# BLDC-DRIVER.net
KiCad netlist of a schematic drawn in Altium Designer
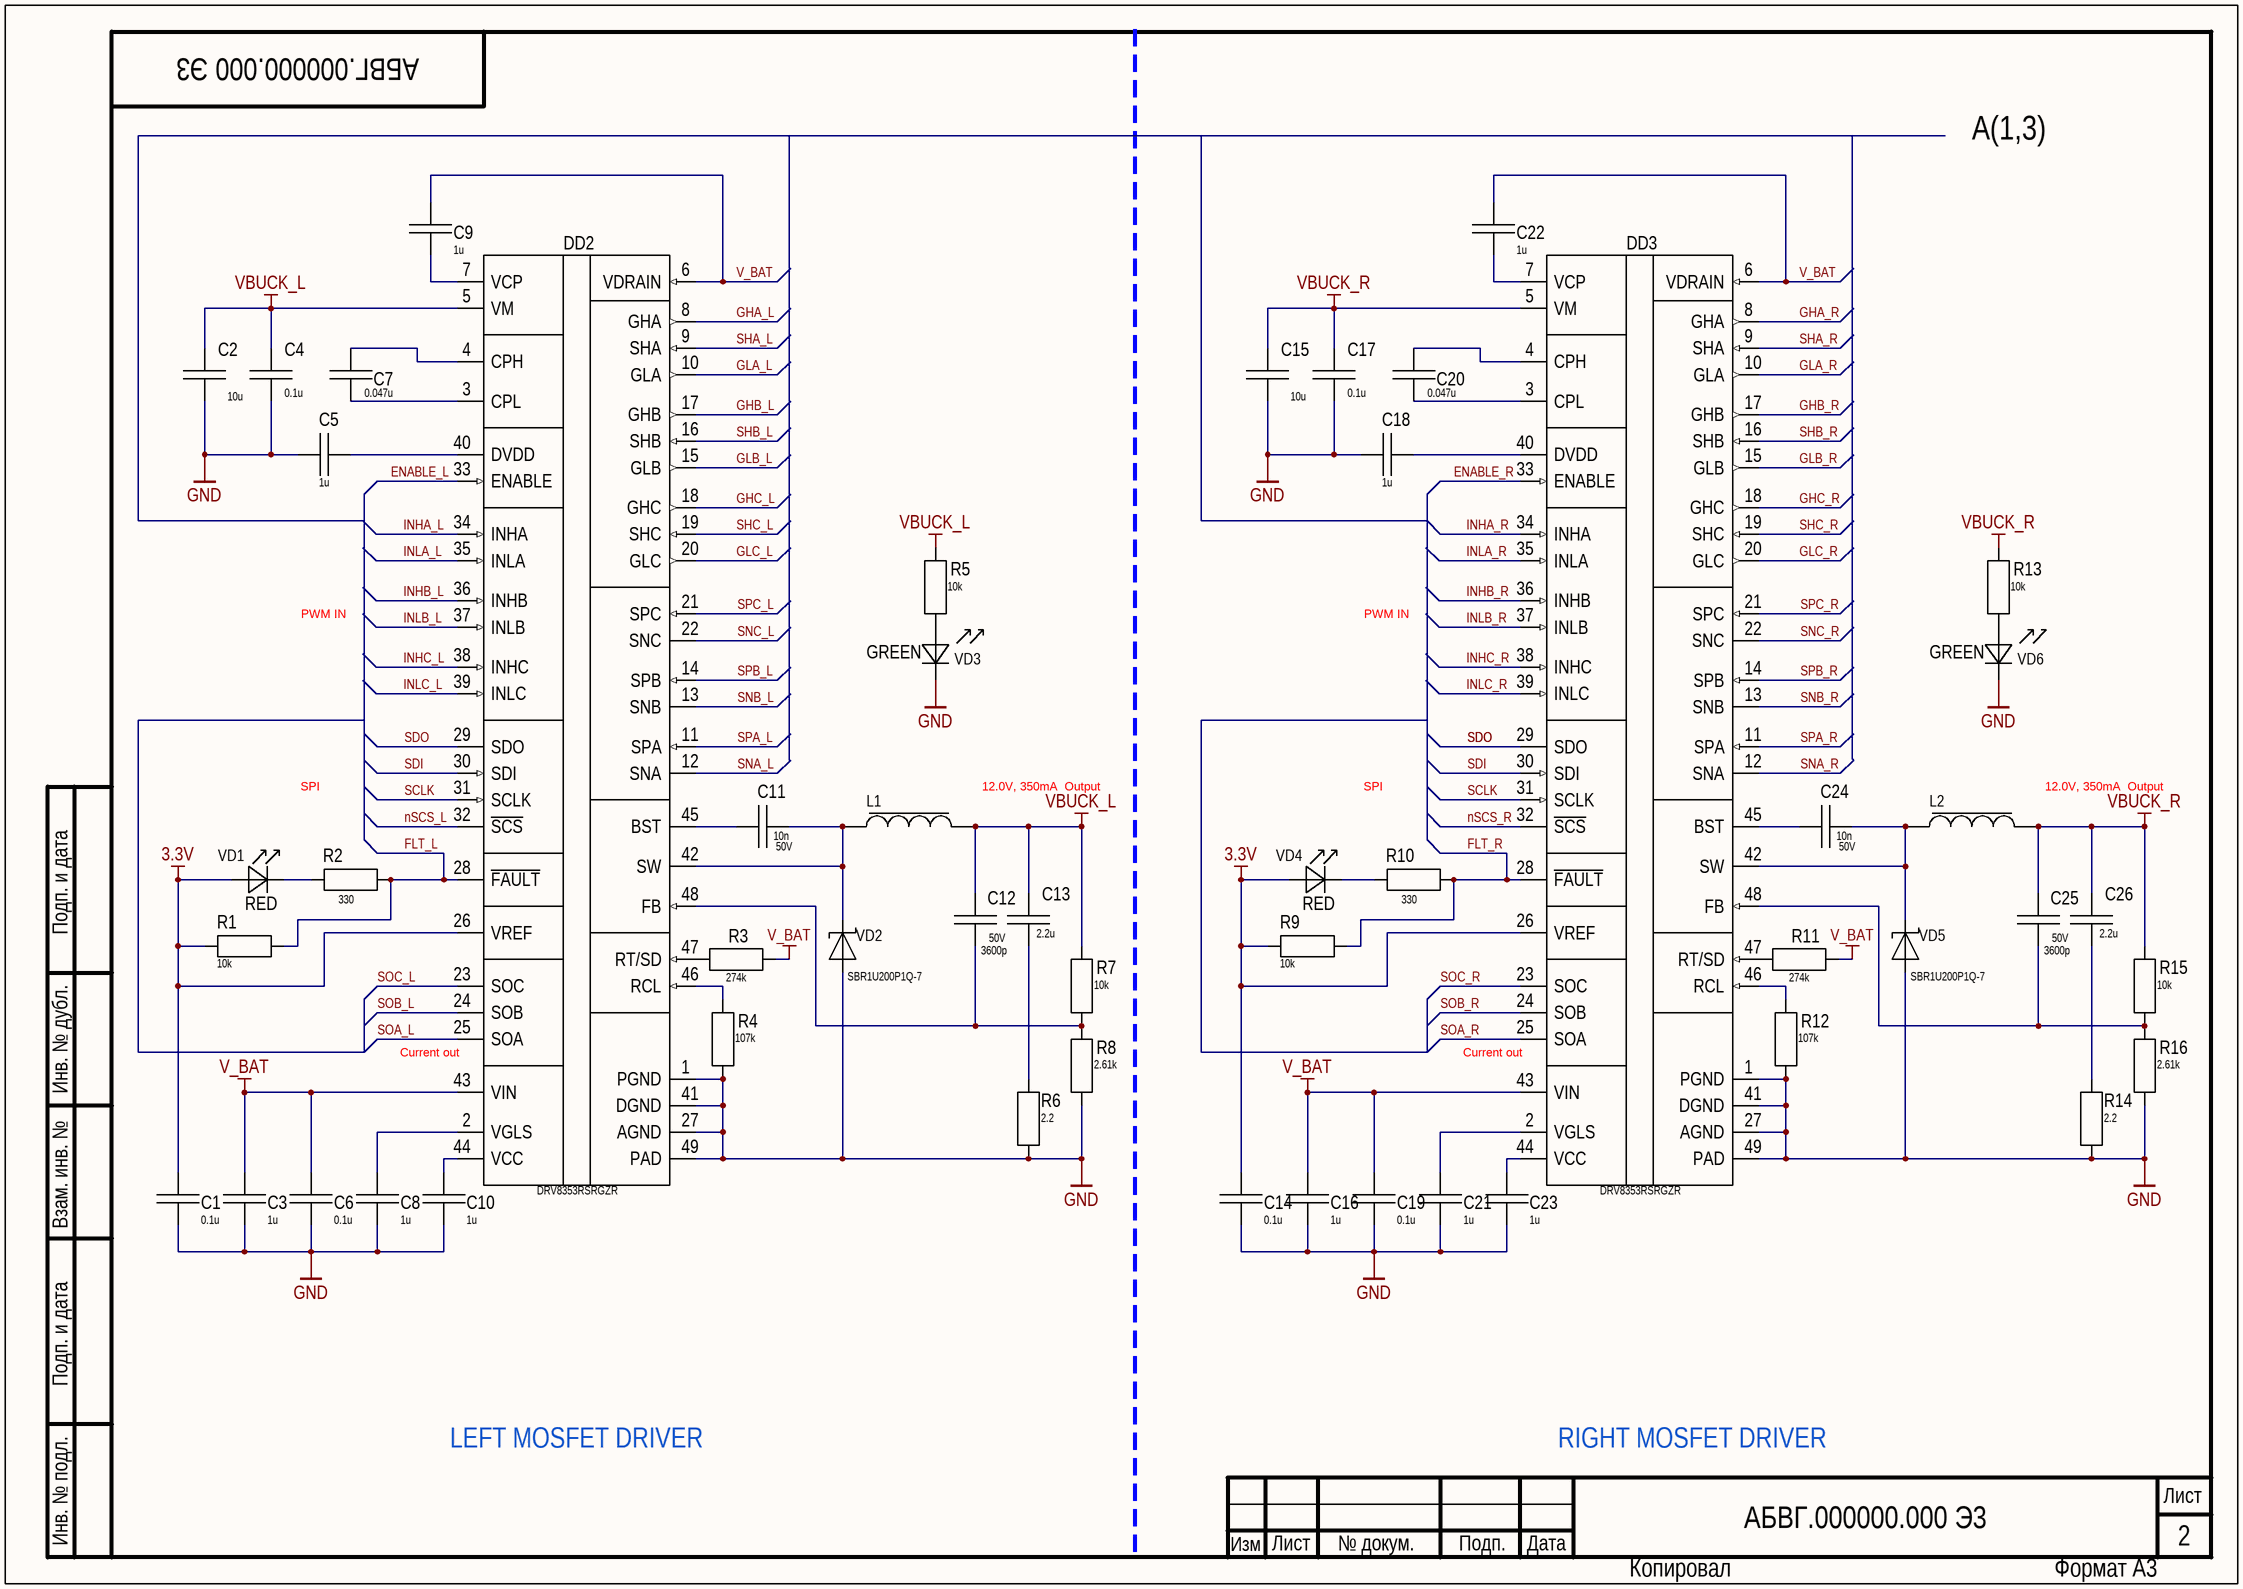
[diagram p0: BLDC-DRIVER.SchDoc]

(export (version "E")
  (design (tool "Eeschema 10.0.6"))
  (components
    (comp (ref "C1")
      (value "0.1u")
      (footprint "CAP: 0402")
      (fields
        (field (name "VOLTAGE") "10V")
        (field (name "PARTNUMBER") "C0402C104K8PAC")
        (field (name "MANUFACTURER") "Kemet")
      )
      (libsource (lib "Fider_Board_Lib") (part "CAP 0402"))
    )
    (comp (ref "C2")
      (value "10u")
      (footprint "CAP: 2220")
      (fields
        (field (name "VOLTAGE") "100V")
        (field (name "TOLERANCE") "10%")
        (field (name "PARTNUMBER") "CGA9N3X7S2A106K230KE")
      )
      (libsource (lib "BKM_SCH_Lib") (part "CAP 2220"))
    )
    (comp (ref "C3")
      (value "1u")
      (footprint "CAP: 1206")
      (fields (field (name "VOLTAGE") "100V") (field (name "TOLERANCE") "10%"))
      (libsource (lib "BKM_SCH_Lib") (part "CAP 1206"))
    )
    (comp (ref "C4")
      (value "0.1u")
      (footprint "CAP: 0805")
      (fields (field (name "VOLTAGE") "100V") (field (name "TOLERANCE") "10%"))
      (libsource (lib "BKM_SCH_Lib") (part "CAP 0805"))
    )
    (comp (ref "C5")
      (value "1u")
      (footprint "CAP: 0603")
      (fields (field (name "VOLTAGE") "16V") (field (name "TOLERANCE") "10%"))
      (libsource (lib "BKM_SCH_Lib") (part "CAP 0603"))
    )
    (comp (ref "C6")
      (value "0.1u")
      (footprint "CAP: 0805")
      (fields (field (name "VOLTAGE") "100V") (field (name "TOLERANCE") "10%"))
      (libsource (lib "BKM_SCH_Lib") (part "CAP 0805"))
    )
    (comp (ref "C7")
      (value "0.047u")
      (footprint "CAP: 0805")
      (fields (field (name "VOLTAGE") "100V") (field (name "TOLERANCE") "10%"))
      (libsource (lib "BKM_SCH_Lib") (part "CAP 0805"))
    )
    (comp (ref "C8")
      (value "1u")
      (footprint "CAP: 0603")
      (fields (field (name "VOLTAGE") "16V") (field (name "TOLERANCE") "10%"))
      (libsource (lib "BKM_SCH_Lib") (part "CAP 0603"))
    )
    (comp (ref "C9")
      (value "1u")
      (footprint "CAP: 1206")
      (fields (field (name "VOLTAGE") "100V") (field (name "TOLERANCE") "10%"))
      (libsource (lib "BKM_SCH_Lib") (part "CAP 1206"))
    )
    (comp (ref "C10")
      (value "1u")
      (footprint "CAP: 0603")
      (fields (field (name "VOLTAGE") "16V") (field (name "TOLERANCE") "10%"))
      (libsource (lib "BKM_SCH_Lib") (part "CAP 0603"))
    )
    (comp (ref "C11")
      (value "10n")
      (footprint "CAP: 0402")
      (fields (field (name "VOLTAGE") "50V") (field (name "TOLERANCE") "10%"))
      (libsource (lib "BKM_SCH_Lib") (part "CAP 0402"))
    )
    (comp (ref "C12")
      (value "3600p")
      (footprint "CAP: 0402")
      (fields (field (name "VOLTAGE") "50V") (field (name "TOLERANCE") "5%"))
      (libsource (lib "BKM_SCH_Lib") (part "CAP 0402"))
    )
    (comp (ref "C13")
      (value "2.2u")
      (footprint "CAP: 0603")
      (fields (field (name "VOLTAGE") "35V") (field (name "TOLERANCE") "10%"))
      (libsource (lib "BKM_SCH_Lib") (part "CAP 0603"))
    )
    (comp (ref "C14")
      (value "0.1u")
      (footprint "CAP: 0402")
      (fields
        (field (name "VOLTAGE") "10V")
        (field (name "PARTNUMBER") "C0402C104K8PAC")
        (field (name "MANUFACTURER") "Kemet")
      )
      (libsource (lib "Fider_Board_Lib") (part "CAP 0402"))
    )
    (comp (ref "C15")
      (value "10u")
      (footprint "CAP: 2220")
      (fields
        (field (name "VOLTAGE") "100V")
        (field (name "TOLERANCE") "10%")
        (field (name "PARTNUMBER") "CGA9N3X7S2A106K230KE")
      )
      (libsource (lib "BKM_SCH_Lib") (part "CAP 2220"))
    )
    (comp (ref "C16")
      (value "1u")
      (footprint "CAP: 1206")
      (fields (field (name "VOLTAGE") "100V") (field (name "TOLERANCE") "10%"))
      (libsource (lib "BKM_SCH_Lib") (part "CAP 1206"))
    )
    (comp (ref "C17")
      (value "0.1u")
      (footprint "CAP: 0805")
      (fields (field (name "VOLTAGE") "100V") (field (name "TOLERANCE") "10%"))
      (libsource (lib "BKM_SCH_Lib") (part "CAP 0805"))
    )
    (comp (ref "C18")
      (value "1u")
      (footprint "CAP: 0603")
      (fields (field (name "VOLTAGE") "16V") (field (name "TOLERANCE") "10%"))
      (libsource (lib "BKM_SCH_Lib") (part "CAP 0603"))
    )
    (comp (ref "C19")
      (value "0.1u")
      (footprint "CAP: 0805")
      (fields (field (name "VOLTAGE") "100V") (field (name "TOLERANCE") "10%"))
      (libsource (lib "BKM_SCH_Lib") (part "CAP 0805"))
    )
    (comp (ref "C20")
      (value "0.047u")
      (footprint "CAP: 0805")
      (fields (field (name "VOLTAGE") "100V") (field (name "TOLERANCE") "10%"))
      (libsource (lib "BKM_SCH_Lib") (part "CAP 0805"))
    )
    (comp (ref "C21")
      (value "1u")
      (footprint "CAP: 0603")
      (fields (field (name "VOLTAGE") "16V") (field (name "TOLERANCE") "10%"))
      (libsource (lib "BKM_SCH_Lib") (part "CAP 0603"))
    )
    (comp (ref "C22")
      (value "1u")
      (footprint "CAP: 1206")
      (fields (field (name "VOLTAGE") "100V") (field (name "TOLERANCE") "10%"))
      (libsource (lib "BKM_SCH_Lib") (part "CAP 1206"))
    )
    (comp (ref "C23")
      (value "1u")
      (footprint "CAP: 0603")
      (fields (field (name "VOLTAGE") "16V") (field (name "TOLERANCE") "10%"))
      (libsource (lib "BKM_SCH_Lib") (part "CAP 0603"))
    )
    (comp (ref "C24")
      (value "10n")
      (footprint "CAP: 0402")
      (fields (field (name "VOLTAGE") "50V") (field (name "TOLERANCE") "10%"))
      (libsource (lib "BKM_SCH_Lib") (part "CAP 0402"))
    )
    (comp (ref "C25")
      (value "3600p")
      (footprint "CAP: 0402")
      (fields (field (name "VOLTAGE") "50V") (field (name "TOLERANCE") "5%"))
      (libsource (lib "BKM_SCH_Lib") (part "CAP 0402"))
    )
    (comp (ref "C26")
      (value "2.2u")
      (footprint "CAP: 0603")
      (fields (field (name "VOLTAGE") "35V") (field (name "TOLERANCE") "10%"))
      (libsource (lib "BKM_SCH_Lib") (part "CAP 0603"))
    )
    (comp (ref "DD2")
      (value "DRV8353RSRGZR")
      (footprint "48-VQFN")
      (libsource (lib "BKM_SCH_Lib") (part "DRV8353RSRGZR"))
    )
    (comp (ref "DD3")
      (value "DRV8353RSRGZR")
      (footprint "48-VQFN")
      (libsource (lib "BKM_SCH_Lib") (part "DRV8353RSRGZR"))
    )
    (comp (ref "L1")
      (value "~")
      (footprint "CustomCase:IND: 2525")
      (libsource (lib "Inductor") (part "Inductor_2525"))
    )
    (comp (ref "L2")
      (value "~")
      (footprint "CustomCase:IND: 2525")
      (libsource (lib "Inductor") (part "Inductor_2525"))
    )
    (comp (ref "R1")
      (value "10k")
      (footprint "RES: 0402")
      (fields (field (name "TOLERANCE") "1%"))
      (libsource (lib "BKM_SCH_Lib") (part "RES 0402"))
    )
    (comp (ref "R2")
      (value "330")
      (footprint "RES: 0402")
      (fields (field (name "TOLERANCE") "1%"))
      (libsource (lib "BKM_SCH_Lib") (part "RES 0402"))
    )
    (comp (ref "R3")
      (value "274k")
      (footprint "RES: 0402")
      (fields (field (name "TOLERANCE") "1%"))
      (libsource (lib "BKM_SCH_Lib") (part "RES 0402"))
    )
    (comp (ref "R4")
      (value "107k")
      (footprint "RES: 0402")
      (fields (field (name "TOLERANCE") "1%"))
      (libsource (lib "BKM_SCH_Lib") (part "RES 0402"))
    )
    (comp (ref "R5")
      (value "10k")
      (footprint "RES: 0402")
      (fields (field (name "TOLERANCE") "1%"))
      (libsource (lib "BKM_SCH_Lib") (part "RES 0402"))
    )
    (comp (ref "R6")
      (value "2.2")
      (footprint "RES: 0603")
      (fields (field (name "TOLERANCE") "1%"))
      (libsource (lib "BKM_SCH_Lib") (part "RES 0603"))
    )
    (comp (ref "R7")
      (value "10k")
      (footprint "RES: 0402")
      (fields (field (name "TOLERANCE") "1%"))
      (libsource (lib "BKM_SCH_Lib") (part "RES 0402"))
    )
    (comp (ref "R8")
      (value "2.61k")
      (footprint "RES: 0402")
      (fields (field (name "TOLERANCE") "1%"))
      (libsource (lib "BKM_SCH_Lib") (part "RES 0402"))
    )
    (comp (ref "R9")
      (value "10k")
      (footprint "RES: 0402")
      (fields (field (name "TOLERANCE") "1%"))
      (libsource (lib "BKM_SCH_Lib") (part "RES 0402"))
    )
    (comp (ref "R10")
      (value "330")
      (footprint "RES: 0402")
      (fields (field (name "TOLERANCE") "1%"))
      (libsource (lib "BKM_SCH_Lib") (part "RES 0402"))
    )
    (comp (ref "R11")
      (value "274k")
      (footprint "RES: 0402")
      (fields (field (name "TOLERANCE") "1%"))
      (libsource (lib "BKM_SCH_Lib") (part "RES 0402"))
    )
    (comp (ref "R12")
      (value "107k")
      (footprint "RES: 0402")
      (fields (field (name "TOLERANCE") "1%"))
      (libsource (lib "BKM_SCH_Lib") (part "RES 0402"))
    )
    (comp (ref "R13")
      (value "10k")
      (footprint "RES: 0402")
      (fields (field (name "TOLERANCE") "1%"))
      (libsource (lib "BKM_SCH_Lib") (part "RES 0402"))
    )
    (comp (ref "R14")
      (value "2.2")
      (footprint "RES: 0603")
      (fields (field (name "TOLERANCE") "1%"))
      (libsource (lib "BKM_SCH_Lib") (part "RES 0603"))
    )
    (comp (ref "R15")
      (value "10k")
      (footprint "RES: 0402")
      (fields (field (name "TOLERANCE") "1%"))
      (libsource (lib "BKM_SCH_Lib") (part "RES 0402"))
    )
    (comp (ref "R16")
      (value "2.61k")
      (footprint "RES: 0402")
      (fields (field (name "TOLERANCE") "1%"))
      (libsource (lib "BKM_SCH_Lib") (part "RES 0402"))
    )
    (comp (ref "VD1")
      (value "RED")
      (footprint "LED: 0402R")
      (fields (field (name "Comment") "Led 0402 RED"))
      (libsource (lib "BKM_SCH_Lib") (part "Led 0402 RED"))
    )
    (comp (ref "VD2")
      (value "~")
      (footprint "DIODE: PowerDI 123")
      (fields
        (field (name "MANUFACTURER") "Diodes Incorporated")
        (field (name "VALUEMANUFACTURERPARTNUMBER") "Schottky diode, 200V, 1A, 850mV, 15pF, PowerDI-123-2, -55...+150°C")
        (field (name "VOLTAGE") "200V")
        (field (name "PARTNUMBER") "SBR1U200P1Q-7")
      )
      (libsource (lib "Diode") (part "Schottky_single"))
    )
    (comp (ref "VD3")
      (value "GREEN")
      (footprint "LED: 0402G")
      (fields (field (name "Comment") "Led 0402 GREEN"))
      (libsource (lib "BKM_SCH_Lib") (part "Led 0402 GREEN"))
    )
    (comp (ref "VD4")
      (value "RED")
      (footprint "LED: 0402R")
      (fields (field (name "Comment") "Led 0402 RED"))
      (libsource (lib "BKM_SCH_Lib") (part "Led 0402 RED"))
    )
    (comp (ref "VD5")
      (value "~")
      (footprint "DIODE: PowerDI 123")
      (fields
        (field (name "MANUFACTURER") "Diodes Incorporated")
        (field (name "VALUEMANUFACTURERPARTNUMBER") "Schottky diode, 200V, 1A, 850mV, 15pF, PowerDI-123-2, -55...+150°C")
        (field (name "VOLTAGE") "200V")
        (field (name "PARTNUMBER") "SBR1U200P1Q-7")
      )
      (libsource (lib "Diode") (part "Schottky_single"))
    )
    (comp (ref "VD6")
      (value "GREEN")
      (footprint "LED: 0402G")
      (fields (field (name "Comment") "Led 0402 GREEN"))
      (libsource (lib "BKM_SCH_Lib") (part "Led 0402 GREEN"))
    )
  )
  (nets
    (net (code "1") (name "/ENABLE_L") (class "Default")
      (node (ref "DD2") (pin "33") (pinfunction "ENABLE_33") (pintype "input"))
    )
    (net (code "2") (name "/ENABLE_R") (class "Default")
      (node (ref "DD3") (pin "33") (pinfunction "ENABLE_33") (pintype "input"))
    )
    (net (code "3") (name "/FLT_L") (class "Default")
      (node (ref "DD2") (pin "28") (pinfunction "FAULT_28") (pintype "open_collector"))
      (node (ref "R1") (pin "1") (pinfunction "1_1") (pintype "passive"))
      (node (ref "R2") (pin "1") (pinfunction "1_1") (pintype "passive"))
    )
    (net (code "4") (name "/FLT_R") (class "Default")
      (node (ref "DD3") (pin "28") (pinfunction "FAULT_28") (pintype "open_collector"))
      (node (ref "R10") (pin "1") (pinfunction "1_1") (pintype "passive"))
      (node (ref "R9") (pin "1") (pinfunction "1_1") (pintype "passive"))
    )
    (net (code "5") (name "/GHA_L") (class "Default")
      (node (ref "DD2") (pin "8") (pinfunction "GHA_8") (pintype "output"))
    )
    (net (code "6") (name "/GHA_R") (class "Default")
      (node (ref "DD3") (pin "8") (pinfunction "GHA_8") (pintype "output"))
    )
    (net (code "7") (name "/GHB_L") (class "Default")
      (node (ref "DD2") (pin "17") (pinfunction "GHB_17") (pintype "output"))
    )
    (net (code "8") (name "/GHB_R") (class "Default")
      (node (ref "DD3") (pin "17") (pinfunction "GHB_17") (pintype "output"))
    )
    (net (code "9") (name "/GHC_L") (class "Default")
      (node (ref "DD2") (pin "18") (pinfunction "GHC_18") (pintype "output"))
    )
    (net (code "10") (name "/GHC_R") (class "Default")
      (node (ref "DD3") (pin "18") (pinfunction "GHC_18") (pintype "output"))
    )
    (net (code "11") (name "/GLA_L") (class "Default")
      (node (ref "DD2") (pin "10") (pinfunction "GLA_10") (pintype "output"))
    )
    (net (code "12") (name "/GLA_R") (class "Default")
      (node (ref "DD3") (pin "10") (pinfunction "GLA_10") (pintype "output"))
    )
    (net (code "13") (name "/GLB_L") (class "Default")
      (node (ref "DD2") (pin "15") (pinfunction "GLB_15") (pintype "output"))
    )
    (net (code "14") (name "/GLB_R") (class "Default")
      (node (ref "DD3") (pin "15") (pinfunction "GLB_15") (pintype "output"))
    )
    (net (code "15") (name "/GLC_L") (class "Default")
      (node (ref "DD2") (pin "20") (pinfunction "GLC_20") (pintype "output"))
    )
    (net (code "16") (name "/GLC_R") (class "Default")
      (node (ref "DD3") (pin "20") (pinfunction "GLC_20") (pintype "output"))
    )
    (net (code "17") (name "/INHA_L") (class "Default")
      (node (ref "DD2") (pin "34") (pinfunction "INHA_34") (pintype "input"))
    )
    (net (code "18") (name "/INHA_R") (class "Default")
      (node (ref "DD3") (pin "34") (pinfunction "INHA_34") (pintype "input"))
    )
    (net (code "19") (name "/INHB_L") (class "Default")
      (node (ref "DD2") (pin "36") (pinfunction "INHB_36") (pintype "input"))
    )
    (net (code "20") (name "/INHB_R") (class "Default")
      (node (ref "DD3") (pin "36") (pinfunction "INHB_36") (pintype "input"))
    )
    (net (code "21") (name "/INHC_L") (class "Default")
      (node (ref "DD2") (pin "38") (pinfunction "INHC_38") (pintype "input"))
    )
    (net (code "22") (name "/INHC_R") (class "Default")
      (node (ref "DD3") (pin "38") (pinfunction "INHC_38") (pintype "input"))
    )
    (net (code "23") (name "/INLA_L") (class "Default")
      (node (ref "DD2") (pin "35") (pinfunction "INLA_35") (pintype "input"))
    )
    (net (code "24") (name "/INLA_R") (class "Default")
      (node (ref "DD3") (pin "35") (pinfunction "INLA_35") (pintype "input"))
    )
    (net (code "25") (name "/INLB_L") (class "Default")
      (node (ref "DD2") (pin "37") (pinfunction "INLB_37") (pintype "input"))
    )
    (net (code "26") (name "/INLB_R") (class "Default")
      (node (ref "DD3") (pin "37") (pinfunction "INLB_37") (pintype "input"))
    )
    (net (code "27") (name "/INLC_L") (class "Default")
      (node (ref "DD2") (pin "39") (pinfunction "INLC_39") (pintype "input"))
    )
    (net (code "28") (name "/INLC_R") (class "Default")
      (node (ref "DD3") (pin "39") (pinfunction "INLC_39") (pintype "input"))
    )
    (net (code "29") (name "/SCLK") (class "Default")
      (node (ref "DD2") (pin "31") (pinfunction "SCLK_31") (pintype "input"))
      (node (ref "DD3") (pin "31") (pinfunction "SCLK_31") (pintype "input"))
    )
    (net (code "30") (name "/SDI") (class "Default")
      (node (ref "DD2") (pin "30") (pinfunction "SDI_30") (pintype "input"))
      (node (ref "DD3") (pin "30") (pinfunction "SDI_30") (pintype "input"))
    )
    (net (code "31") (name "/SDO") (class "Default")
      (node (ref "DD2") (pin "29") (pinfunction "SDO_29") (pintype "passive"))
      (node (ref "DD3") (pin "29") (pinfunction "SDO_29") (pintype "passive"))
    )
    (net (code "32") (name "/SHA_L") (class "Default")
      (node (ref "DD2") (pin "9") (pinfunction "SHA_9") (pintype "input"))
    )
    (net (code "33") (name "/SHA_R") (class "Default")
      (node (ref "DD3") (pin "9") (pinfunction "SHA_9") (pintype "input"))
    )
    (net (code "34") (name "/SHB_L") (class "Default")
      (node (ref "DD2") (pin "16") (pinfunction "SHB_16") (pintype "input"))
    )
    (net (code "35") (name "/SHB_R") (class "Default")
      (node (ref "DD3") (pin "16") (pinfunction "SHB_16") (pintype "input"))
    )
    (net (code "36") (name "/SHC_L") (class "Default")
      (node (ref "DD2") (pin "19") (pinfunction "SHC_19") (pintype "input"))
    )
    (net (code "37") (name "/SHC_R") (class "Default")
      (node (ref "DD3") (pin "19") (pinfunction "SHC_19") (pintype "input"))
    )
    (net (code "38") (name "/SNA_L") (class "Default")
      (node (ref "DD2") (pin "12") (pinfunction "SNA_12") (pintype "passive"))
    )
    (net (code "39") (name "/SNA_R") (class "Default")
      (node (ref "DD3") (pin "12") (pinfunction "SNA_12") (pintype "passive"))
    )
    (net (code "40") (name "/SNB_L") (class "Default")
      (node (ref "DD2") (pin "13") (pinfunction "SNB_13") (pintype "passive"))
    )
    (net (code "41") (name "/SNB_R") (class "Default")
      (node (ref "DD3") (pin "13") (pinfunction "SNB_13") (pintype "passive"))
    )
    (net (code "42") (name "/SNC_L") (class "Default")
      (node (ref "DD2") (pin "22") (pinfunction "SNC_22") (pintype "passive"))
    )
    (net (code "43") (name "/SNC_R") (class "Default")
      (node (ref "DD3") (pin "22") (pinfunction "SNC_22") (pintype "passive"))
    )
    (net (code "44") (name "/SOA_L") (class "Default")
      (node (ref "DD2") (pin "25") (pinfunction "SOA_25") (pintype "passive"))
    )
    (net (code "45") (name "/SOA_R") (class "Default")
      (node (ref "DD3") (pin "25") (pinfunction "SOA_25") (pintype "passive"))
    )
    (net (code "46") (name "/SOB_L") (class "Default")
      (node (ref "DD2") (pin "24") (pinfunction "SOB_24") (pintype "passive"))
    )
    (net (code "47") (name "/SOB_R") (class "Default")
      (node (ref "DD3") (pin "24") (pinfunction "SOB_24") (pintype "passive"))
    )
    (net (code "48") (name "/SOC_L") (class "Default")
      (node (ref "DD2") (pin "23") (pinfunction "SOC_23") (pintype "passive"))
    )
    (net (code "49") (name "/SOC_R") (class "Default")
      (node (ref "DD3") (pin "23") (pinfunction "SOC_23") (pintype "passive"))
    )
    (net (code "50") (name "/SPA_L") (class "Default")
      (node (ref "DD2") (pin "11") (pinfunction "SPA_11") (pintype "input"))
    )
    (net (code "51") (name "/SPA_R") (class "Default")
      (node (ref "DD3") (pin "11") (pinfunction "SPA_11") (pintype "input"))
    )
    (net (code "52") (name "/SPB_L") (class "Default")
      (node (ref "DD2") (pin "14") (pinfunction "SPB_14") (pintype "input"))
    )
    (net (code "53") (name "/SPB_R") (class "Default")
      (node (ref "DD3") (pin "14") (pinfunction "SPB_14") (pintype "input"))
    )
    (net (code "54") (name "/SPC_L") (class "Default")
      (node (ref "DD2") (pin "21") (pinfunction "SPC_21") (pintype "input"))
    )
    (net (code "55") (name "/SPC_R") (class "Default")
      (node (ref "DD3") (pin "21") (pinfunction "SPC_21") (pintype "input"))
    )
    (net (code "56") (name "/nSCS_L") (class "Default")
      (node (ref "DD2") (pin "32") (pinfunction "SCS_32") (pintype "passive"))
    )
    (net (code "57") (name "/nSCS_R") (class "Default")
      (node (ref "DD3") (pin "32") (pinfunction "SCS_32") (pintype "passive"))
    )
    (net (code "58") (name "3.3V") (class "Default")
      (node (ref "C1") (pin "1") (pinfunction "1_1") (pintype "passive"))
      (node (ref "C14") (pin "1") (pinfunction "1_1") (pintype "passive"))
      (node (ref "DD2") (pin "26") (pinfunction "VREF_26") (pintype "passive"))
      (node (ref "DD3") (pin "26") (pinfunction "VREF_26") (pintype "passive"))
      (node (ref "R1") (pin "2") (pinfunction "2_2") (pintype "passive"))
      (node (ref "R9") (pin "2") (pinfunction "2_2") (pintype "passive"))
      (node (ref "VD1") (pin "1") (pinfunction "1_1") (pintype "passive"))
      (node (ref "VD4") (pin "1") (pinfunction "1_1") (pintype "passive"))
    )
    (net (code "59") (name "GND") (class "Default")
      (node (ref "C1") (pin "2") (pinfunction "2_2") (pintype "passive"))
      (node (ref "C10") (pin "1") (pinfunction "1_1") (pintype "passive"))
      (node (ref "C14") (pin "2") (pinfunction "2_2") (pintype "passive"))
      (node (ref "C15") (pin "1") (pinfunction "1_1") (pintype "passive"))
      (node (ref "C16") (pin "1") (pinfunction "1_1") (pintype "passive"))
      (node (ref "C17") (pin "1") (pinfunction "1_1") (pintype "passive"))
      (node (ref "C18") (pin "2") (pinfunction "2_2") (pintype "passive"))
      (node (ref "C19") (pin "1") (pinfunction "1_1") (pintype "passive"))
      (node (ref "C2") (pin "1") (pinfunction "1_1") (pintype "passive"))
      (node (ref "C21") (pin "1") (pinfunction "1_1") (pintype "passive"))
      (node (ref "C23") (pin "1") (pinfunction "1_1") (pintype "passive"))
      (node (ref "C3") (pin "1") (pinfunction "1_1") (pintype "passive"))
      (node (ref "C4") (pin "1") (pinfunction "1_1") (pintype "passive"))
      (node (ref "C5") (pin "2") (pinfunction "2_2") (pintype "passive"))
      (node (ref "C6") (pin "1") (pinfunction "1_1") (pintype "passive"))
      (node (ref "C8") (pin "1") (pinfunction "1_1") (pintype "passive"))
      (node (ref "DD2") (pin "1") (pinfunction "PGND_1") (pintype "power_in"))
      (node (ref "DD2") (pin "27") (pinfunction "AGND_27") (pintype "power_in"))
      (node (ref "DD2") (pin "41") (pinfunction "DGND_41") (pintype "power_in"))
      (node (ref "DD2") (pin "49") (pinfunction "PAD_49") (pintype "power_in"))
      (node (ref "DD3") (pin "1") (pinfunction "PGND_1") (pintype "power_in"))
      (node (ref "DD3") (pin "27") (pinfunction "AGND_27") (pintype "power_in"))
      (node (ref "DD3") (pin "41") (pinfunction "DGND_41") (pintype "power_in"))
      (node (ref "DD3") (pin "49") (pinfunction "PAD_49") (pintype "power_in"))
      (node (ref "R12") (pin "1") (pinfunction "1_1") (pintype "passive"))
      (node (ref "R14") (pin "1") (pinfunction "1_1") (pintype "passive"))
      (node (ref "R16") (pin "1") (pinfunction "1_1") (pintype "passive"))
      (node (ref "R4") (pin "1") (pinfunction "1_1") (pintype "passive"))
      (node (ref "R6") (pin "1") (pinfunction "1_1") (pintype "passive"))
      (node (ref "R8") (pin "1") (pinfunction "1_1") (pintype "passive"))
      (node (ref "VD2") (pin "1") (pinfunction "1_1") (pintype "passive"))
      (node (ref "VD3") (pin "2") (pinfunction "2_2") (pintype "passive"))
      (node (ref "VD5") (pin "1") (pinfunction "1_1") (pintype "passive"))
      (node (ref "VD6") (pin "2") (pinfunction "2_2") (pintype "passive"))
    )
    (net (code "60") (name "Net-(C13-Pad1)") (class "Default")
      (node (ref "C13") (pin "1") (pinfunction "1_1") (pintype "passive"))
      (node (ref "R6") (pin "2") (pinfunction "2_2") (pintype "passive"))
    )
    (net (code "61") (name "Net-(C26-Pad1)") (class "Default")
      (node (ref "C26") (pin "1") (pinfunction "1_1") (pintype "passive"))
      (node (ref "R14") (pin "2") (pinfunction "2_2") (pintype "passive"))
    )
    (net (code "62") (name "Net-(DD2-BST)") (class "Default")
      (node (ref "C11") (pin "1") (pinfunction "1_1") (pintype "passive"))
      (node (ref "DD2") (pin "45") (pinfunction "BST_45") (pintype "power_in"))
    )
    (net (code "63") (name "Net-(DD2-CPH)") (class "Default")
      (node (ref "C7") (pin "2") (pinfunction "2_2") (pintype "passive"))
      (node (ref "DD2") (pin "4") (pinfunction "CPH_4") (pintype "passive"))
    )
    (net (code "64") (name "Net-(DD2-CPL)") (class "Default")
      (node (ref "C7") (pin "1") (pinfunction "1_1") (pintype "passive"))
      (node (ref "DD2") (pin "3") (pinfunction "CPL_3") (pintype "passive"))
    )
    (net (code "65") (name "Net-(DD2-DVDD)") (class "Default")
      (node (ref "C5") (pin "1") (pinfunction "1_1") (pintype "passive"))
      (node (ref "DD2") (pin "40") (pinfunction "DVDD_40") (pintype "power_in"))
    )
    (net (code "66") (name "Net-(DD2-FB)") (class "Default")
      (node (ref "C12") (pin "1") (pinfunction "1_1") (pintype "passive"))
      (node (ref "DD2") (pin "48") (pinfunction "FB_48") (pintype "input"))
      (node (ref "R7") (pin "1") (pinfunction "1_1") (pintype "passive"))
      (node (ref "R8") (pin "2") (pinfunction "2_2") (pintype "passive"))
    )
    (net (code "67") (name "Net-(DD2-RCL)") (class "Default")
      (node (ref "DD2") (pin "46") (pinfunction "RCL_46") (pintype "input"))
      (node (ref "R4") (pin "2") (pinfunction "2_2") (pintype "passive"))
    )
    (net (code "68") (name "Net-(DD2-RT{slash}SD)") (class "Default")
      (node (ref "DD2") (pin "47") (pinfunction "RT/SD_47") (pintype "input"))
      (node (ref "R3") (pin "2") (pinfunction "2_2") (pintype "passive"))
    )
    (net (code "69") (name "Net-(DD2-SW)") (class "Default")
      (node (ref "C11") (pin "2") (pinfunction "2_2") (pintype "passive"))
      (node (ref "DD2") (pin "42") (pinfunction "SW_42") (pintype "power_in"))
      (node (ref "L1") (pin "2") (pinfunction "2_2") (pintype "passive"))
      (node (ref "VD2") (pin "2") (pinfunction "2_2") (pintype "passive"))
    )
    (net (code "70") (name "Net-(DD2-VCC)") (class "Default")
      (node (ref "C10") (pin "2") (pinfunction "2_2") (pintype "passive"))
      (node (ref "DD2") (pin "44") (pinfunction "VCC_44") (pintype "power_in"))
    )
    (net (code "71") (name "Net-(DD2-VCP)") (class "Default")
      (node (ref "C9") (pin "1") (pinfunction "1_1") (pintype "passive"))
      (node (ref "DD2") (pin "7") (pinfunction "VCP_7") (pintype "power_in"))
    )
    (net (code "72") (name "Net-(DD2-VGLS)") (class "Default")
      (node (ref "C8") (pin "2") (pinfunction "2_2") (pintype "passive"))
      (node (ref "DD2") (pin "2") (pinfunction "VGLS_2") (pintype "power_in"))
    )
    (net (code "73") (name "Net-(DD3-BST)") (class "Default")
      (node (ref "C24") (pin "1") (pinfunction "1_1") (pintype "passive"))
      (node (ref "DD3") (pin "45") (pinfunction "BST_45") (pintype "power_in"))
    )
    (net (code "74") (name "Net-(DD3-CPH)") (class "Default")
      (node (ref "C20") (pin "2") (pinfunction "2_2") (pintype "passive"))
      (node (ref "DD3") (pin "4") (pinfunction "CPH_4") (pintype "passive"))
    )
    (net (code "75") (name "Net-(DD3-CPL)") (class "Default")
      (node (ref "C20") (pin "1") (pinfunction "1_1") (pintype "passive"))
      (node (ref "DD3") (pin "3") (pinfunction "CPL_3") (pintype "passive"))
    )
    (net (code "76") (name "Net-(DD3-DVDD)") (class "Default")
      (node (ref "C18") (pin "1") (pinfunction "1_1") (pintype "passive"))
      (node (ref "DD3") (pin "40") (pinfunction "DVDD_40") (pintype "power_in"))
    )
    (net (code "77") (name "Net-(DD3-FB)") (class "Default")
      (node (ref "C25") (pin "1") (pinfunction "1_1") (pintype "passive"))
      (node (ref "DD3") (pin "48") (pinfunction "FB_48") (pintype "input"))
      (node (ref "R15") (pin "1") (pinfunction "1_1") (pintype "passive"))
      (node (ref "R16") (pin "2") (pinfunction "2_2") (pintype "passive"))
    )
    (net (code "78") (name "Net-(DD3-RCL)") (class "Default")
      (node (ref "DD3") (pin "46") (pinfunction "RCL_46") (pintype "input"))
      (node (ref "R12") (pin "2") (pinfunction "2_2") (pintype "passive"))
    )
    (net (code "79") (name "Net-(DD3-RT{slash}SD)") (class "Default")
      (node (ref "DD3") (pin "47") (pinfunction "RT/SD_47") (pintype "input"))
      (node (ref "R11") (pin "2") (pinfunction "2_2") (pintype "passive"))
    )
    (net (code "80") (name "Net-(DD3-SW)") (class "Default")
      (node (ref "C24") (pin "2") (pinfunction "2_2") (pintype "passive"))
      (node (ref "DD3") (pin "42") (pinfunction "SW_42") (pintype "power_in"))
      (node (ref "L2") (pin "2") (pinfunction "2_2") (pintype "passive"))
      (node (ref "VD5") (pin "2") (pinfunction "2_2") (pintype "passive"))
    )
    (net (code "81") (name "Net-(DD3-VCC)") (class "Default")
      (node (ref "C23") (pin "2") (pinfunction "2_2") (pintype "passive"))
      (node (ref "DD3") (pin "44") (pinfunction "VCC_44") (pintype "power_in"))
    )
    (net (code "82") (name "Net-(DD3-VCP)") (class "Default")
      (node (ref "C22") (pin "1") (pinfunction "1_1") (pintype "passive"))
      (node (ref "DD3") (pin "7") (pinfunction "VCP_7") (pintype "power_in"))
    )
    (net (code "83") (name "Net-(DD3-VGLS)") (class "Default")
      (node (ref "C21") (pin "2") (pinfunction "2_2") (pintype "passive"))
      (node (ref "DD3") (pin "2") (pinfunction "VGLS_2") (pintype "power_in"))
    )
    (net (code "84") (name "Net-(R2-Pad2)") (class "Default")
      (node (ref "R2") (pin "2") (pinfunction "2_2") (pintype "passive"))
      (node (ref "VD1") (pin "2") (pinfunction "2_2") (pintype "passive"))
    )
    (net (code "85") (name "Net-(R5-Pad1)") (class "Default")
      (node (ref "R5") (pin "1") (pinfunction "1_1") (pintype "passive"))
      (node (ref "VD3") (pin "1") (pinfunction "1_1") (pintype "passive"))
    )
    (net (code "86") (name "Net-(R10-Pad2)") (class "Default")
      (node (ref "R10") (pin "2") (pinfunction "2_2") (pintype "passive"))
      (node (ref "VD4") (pin "2") (pinfunction "2_2") (pintype "passive"))
    )
    (net (code "87") (name "Net-(R13-Pad1)") (class "Default")
      (node (ref "R13") (pin "1") (pinfunction "1_1") (pintype "passive"))
      (node (ref "VD6") (pin "1") (pinfunction "1_1") (pintype "passive"))
    )
    (net (code "88") (name "VBUCK_L") (class "Default")
      (node (ref "C12") (pin "2") (pinfunction "2_2") (pintype "passive"))
      (node (ref "C13") (pin "2") (pinfunction "2_2") (pintype "passive"))
      (node (ref "C2") (pin "2") (pinfunction "2_2") (pintype "passive"))
      (node (ref "C4") (pin "2") (pinfunction "2_2") (pintype "passive"))
      (node (ref "DD2") (pin "5") (pinfunction "VM_5") (pintype "power_in"))
      (node (ref "L1") (pin "1") (pinfunction "1_1") (pintype "passive"))
      (node (ref "R5") (pin "2") (pinfunction "2_2") (pintype "passive"))
      (node (ref "R7") (pin "2") (pinfunction "2_2") (pintype "passive"))
    )
    (net (code "89") (name "VBUCK_R") (class "Default")
      (node (ref "C15") (pin "2") (pinfunction "2_2") (pintype "passive"))
      (node (ref "C17") (pin "2") (pinfunction "2_2") (pintype "passive"))
      (node (ref "C25") (pin "2") (pinfunction "2_2") (pintype "passive"))
      (node (ref "C26") (pin "2") (pinfunction "2_2") (pintype "passive"))
      (node (ref "DD3") (pin "5") (pinfunction "VM_5") (pintype "power_in"))
      (node (ref "L2") (pin "1") (pinfunction "1_1") (pintype "passive"))
      (node (ref "R13") (pin "2") (pinfunction "2_2") (pintype "passive"))
      (node (ref "R15") (pin "2") (pinfunction "2_2") (pintype "passive"))
    )
    (net (code "90") (name "V_BAT") (class "Default")
      (node (ref "C16") (pin "2") (pinfunction "2_2") (pintype "passive"))
      (node (ref "C19") (pin "2") (pinfunction "2_2") (pintype "passive"))
      (node (ref "C22") (pin "2") (pinfunction "2_2") (pintype "passive"))
      (node (ref "C3") (pin "2") (pinfunction "2_2") (pintype "passive"))
      (node (ref "C6") (pin "2") (pinfunction "2_2") (pintype "passive"))
      (node (ref "C9") (pin "2") (pinfunction "2_2") (pintype "passive"))
      (node (ref "DD2") (pin "43") (pinfunction "VIN_43") (pintype "power_in"))
      (node (ref "DD2") (pin "6") (pinfunction "VDRAIN_6") (pintype "input"))
      (node (ref "DD3") (pin "43") (pinfunction "VIN_43") (pintype "power_in"))
      (node (ref "DD3") (pin "6") (pinfunction "VDRAIN_6") (pintype "input"))
      (node (ref "R11") (pin "1") (pinfunction "1_1") (pintype "passive"))
      (node (ref "R3") (pin "1") (pinfunction "1_1") (pintype "passive"))
    )
  )
)
